# Buttons-Sch-EasyEDA.net
KiCad netlist of a schematic drawn in EasyEDA
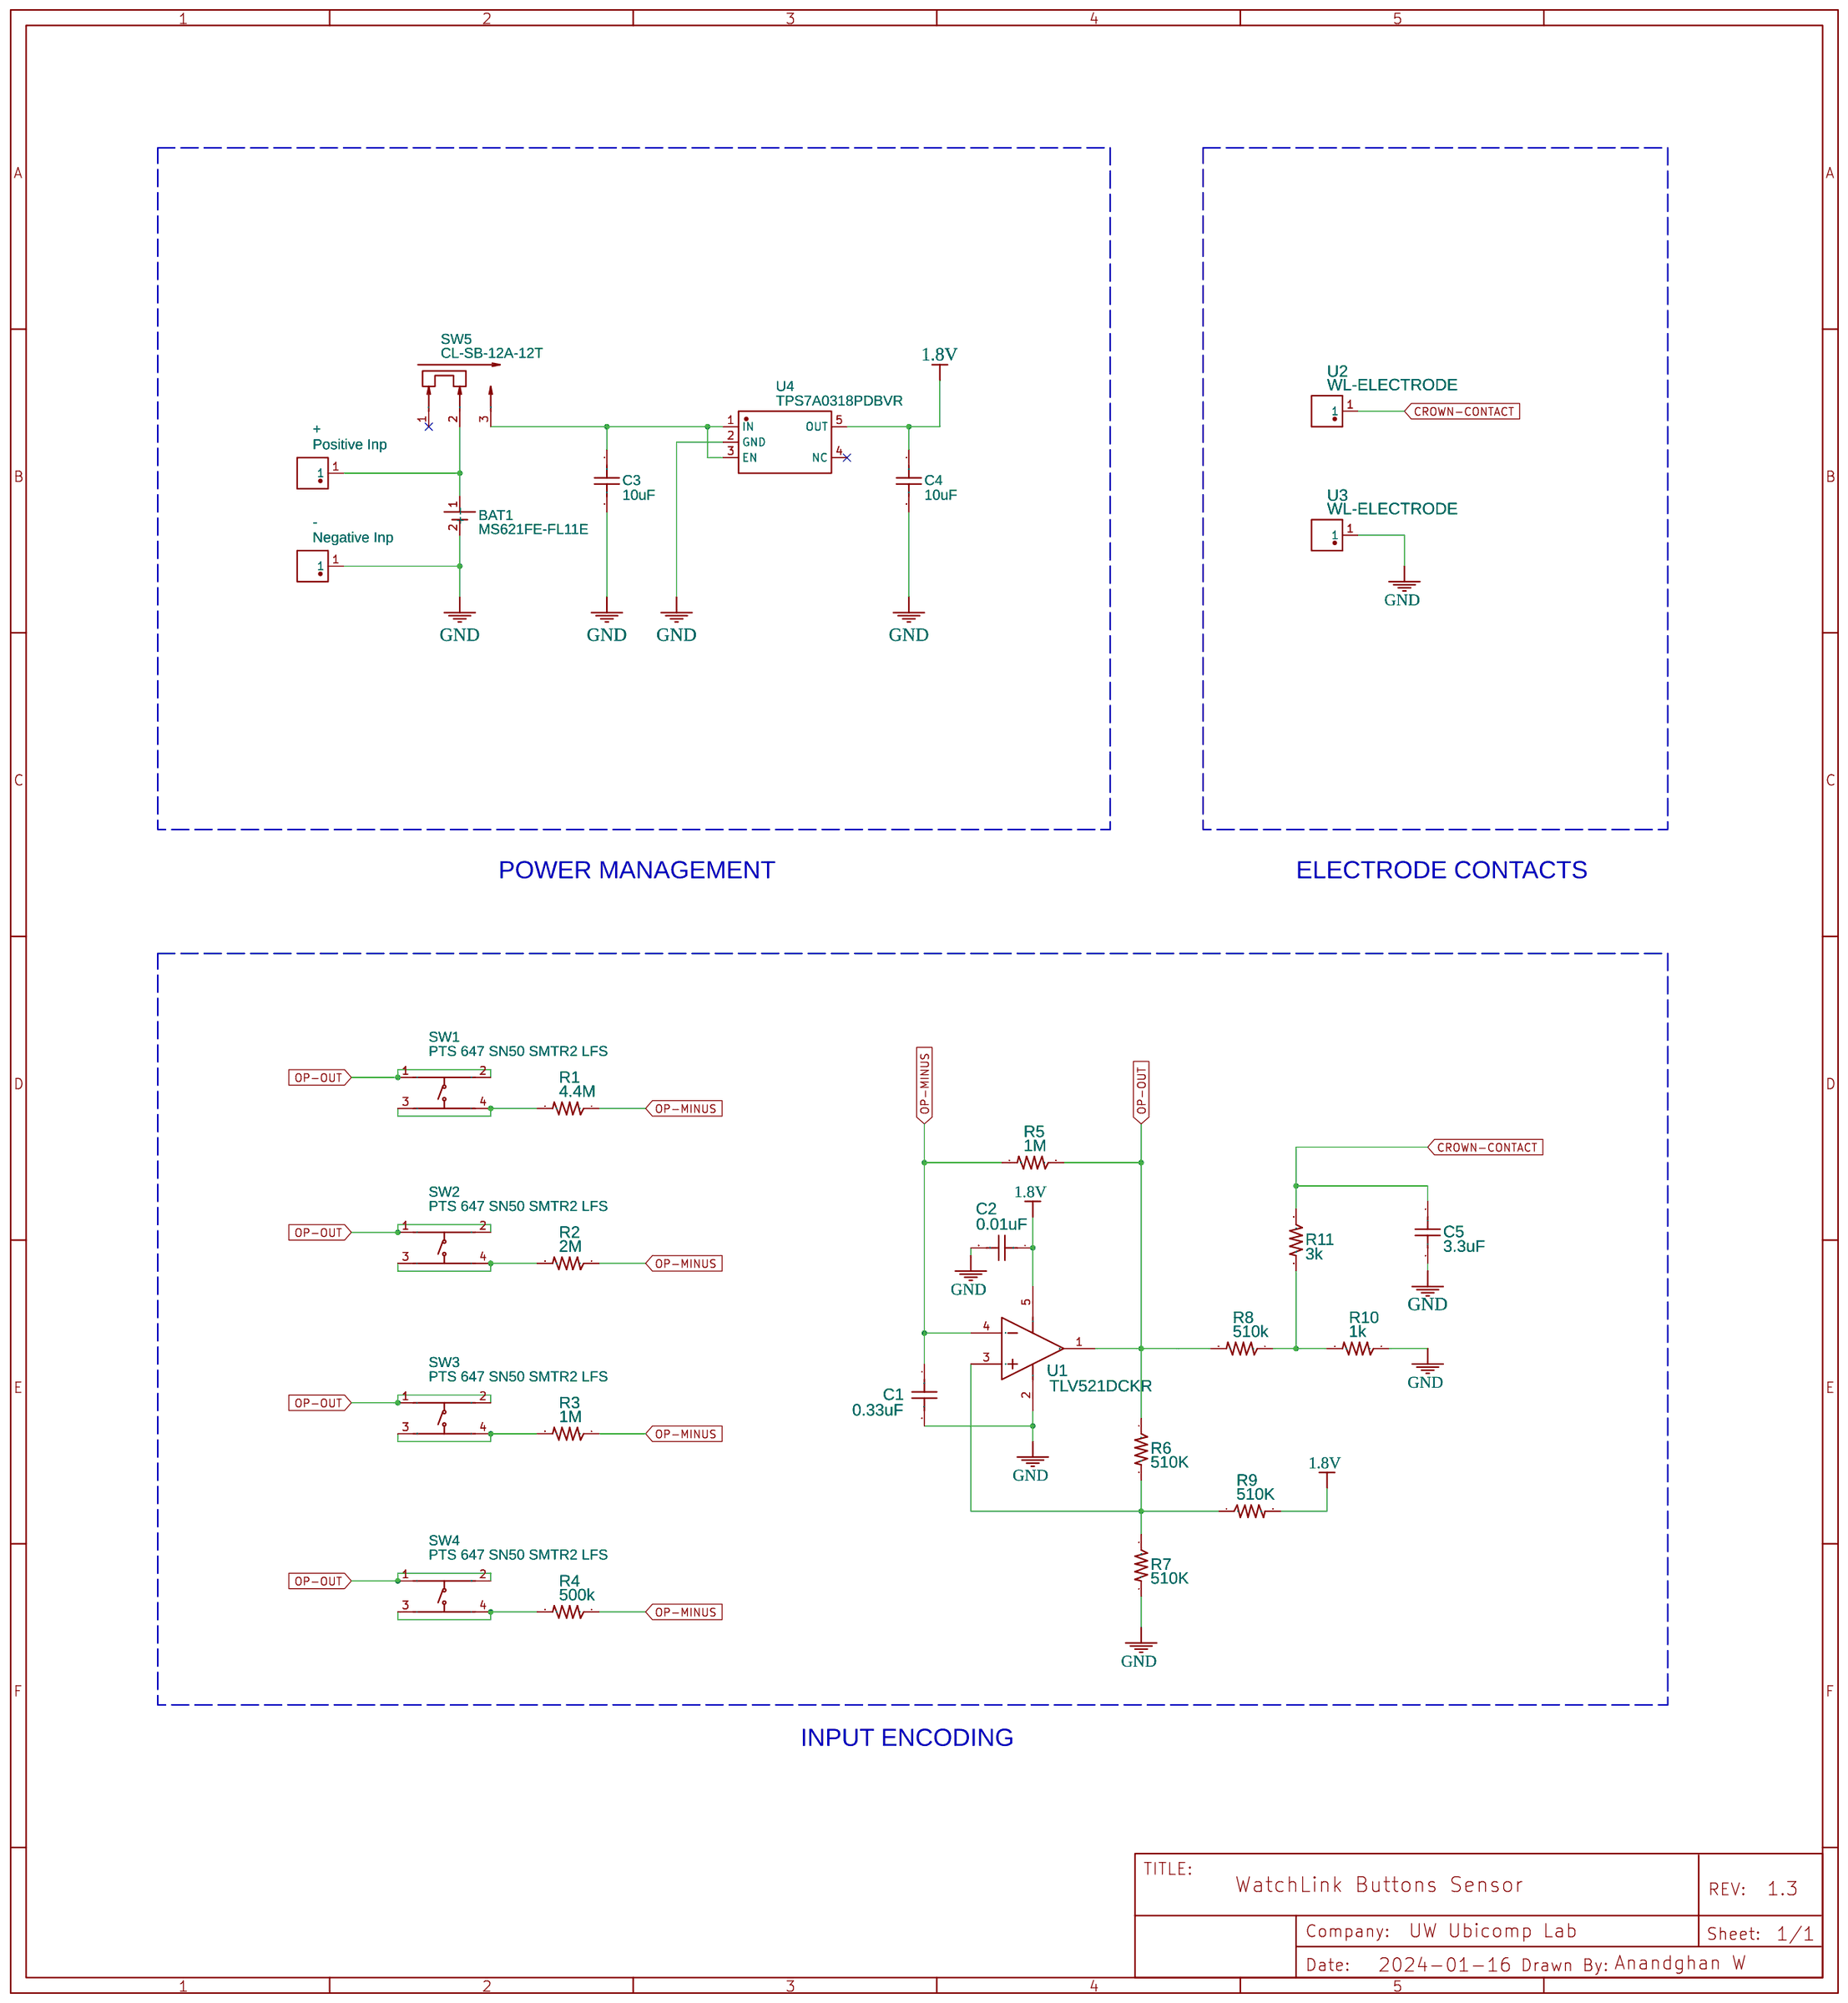
[diagram p0: schematic sheet]

(export (version "E")
  (design (tool "Eeschema 10.0.6"))
  (components
    (comp (ref "+")
      (value "Positive Inp")
      (fields (field (name "Manufacturer Part") "POGO pin探针"))
      (libsource (lib "") (part "WL-ELECTRODE_1"))
    )
    (comp (ref "-")
      (value "Negative Inp")
      (fields (field (name "Manufacturer Part") "POGO pin探针"))
      (libsource (lib "") (part "WL-ELECTRODE_2"))
    )
    (comp (ref "BAT1")
      (value "MS621FE-FL11E")
      (fields (field (name "Manufacturer Part") "ML621 / ML614") (field (name "Manufacturer") "Panasonic"))
      (libsource (lib "") (part "ML614 / ML621 - COIN CELL"))
    )
    (comp (ref "C1")
      (value "0.33uF")
      (fields
        (field (name "Manufacturer Part") "CC0402JRX7R8BB473")
        (field (name "Manufacturer") "YAGEO(国巨)")
      )
      (libsource (lib "") (part "CC0402JRX7R8BB473"))
    )
    (comp (ref "C2")
      (value "0.01uF")
      (fields
        (field (name "Manufacturer Part") "CC0402JRX7R8BB473")
        (field (name "Manufacturer") "YAGEO(国巨)")
      )
      (libsource (lib "") (part "CC0402JRX7R8BB473_1"))
    )
    (comp (ref "C3")
      (value "10uF")
      (fields
        (field (name "Manufacturer Part") "CC0402JRX7R8BB473")
        (field (name "Manufacturer") "YAGEO(国巨)")
      )
      (libsource (lib "") (part "CC0402JRX7R8BB473"))
    )
    (comp (ref "C4")
      (value "10uF")
      (fields
        (field (name "Manufacturer Part") "CC0402JRX7R8BB473")
        (field (name "Manufacturer") "YAGEO(国巨)")
      )
      (libsource (lib "") (part "CC0402JRX7R8BB473"))
    )
    (comp (ref "C5")
      (value "3.3uF")
      (fields
        (field (name "Manufacturer Part") "CC0402JRX7R8BB473")
        (field (name "Manufacturer") "YAGEO(国巨)")
      )
      (libsource (lib "") (part "CC0402JRX7R8BB473"))
    )
    (comp (ref "R1") (value "4.4M") (libsource (lib "") (part "R-US_R0402_2")))
    (comp (ref "R2") (value "2M") (libsource (lib "") (part "R-US_R0402_2")))
    (comp (ref "R3") (value "1M") (libsource (lib "") (part "R-US_R0402_2")))
    (comp (ref "R4") (value "500k") (libsource (lib "") (part "R-US_R0402_2")))
    (comp (ref "R5") (value "1M") (libsource (lib "") (part "R-US_R0402_2")))
    (comp (ref "R6") (value "510K") (libsource (lib "") (part "R-US_R0402")))
    (comp (ref "R7") (value "510K") (libsource (lib "") (part "R-US_R0402")))
    (comp (ref "R8") (value "510k") (libsource (lib "") (part "R-US_R0402_2")))
    (comp (ref "R9") (value "510K") (libsource (lib "") (part "R-US_R0402_1")))
    (comp (ref "R10") (value "1k") (libsource (lib "") (part "R-US_R0402_2")))
    (comp (ref "R11") (value "3k") (libsource (lib "") (part "R-US_R0402")))
    (comp (ref "SW1")
      (value "PTS 647 SN50 SMTR2 LFS")
      (fields (field (name "Manufacturer Part") "PTS647SN50SMTR2LFS") (field (name "Manufacturer") "C&K"))
      (libsource (lib "") (part "PTS 647 SN50 SMTR2 LFS"))
    )
    (comp (ref "SW2")
      (value "PTS 647 SN50 SMTR2 LFS")
      (fields (field (name "Manufacturer Part") "PTS647SN50SMTR2LFS") (field (name "Manufacturer") "C&K"))
      (libsource (lib "") (part "PTS 647 SN50 SMTR2 LFS"))
    )
    (comp (ref "SW3")
      (value "PTS 647 SN50 SMTR2 LFS")
      (fields (field (name "Manufacturer Part") "PTS647SN50SMTR2LFS") (field (name "Manufacturer") "C&K"))
      (libsource (lib "") (part "PTS 647 SN50 SMTR2 LFS"))
    )
    (comp (ref "SW4")
      (value "PTS 647 SN50 SMTR2 LFS")
      (fields (field (name "Manufacturer Part") "PTS647SN50SMTR2LFS") (field (name "Manufacturer") "C&K"))
      (libsource (lib "") (part "PTS 647 SN50 SMTR2 LFS"))
    )
    (comp (ref "SW5")
      (value "CL-SB-12A-12T")
      (fields (field (name "Manufacturer") "NIDEC(尼得科)"))
      (libsource (lib "") (part "CL-SB-12A-12T"))
    )
    (comp (ref "U1")
      (value "TLV521DCKR")
      (fields (field (name "Manufacturer") "TI(德州仪器)"))
      (libsource (lib "") (part "TLV521DCKR"))
    )
    (comp (ref "U2")
      (value "WL-ELECTRODE")
      (fields (field (name "Manufacturer Part") "POGO pin探针"))
      (libsource (lib "") (part "WL-ELECTRODE"))
    )
    (comp (ref "U3")
      (value "WL-ELECTRODE")
      (fields (field (name "Manufacturer Part") "POGO pin探针"))
      (libsource (lib "") (part "WL-ELECTRODE"))
    )
    (comp (ref "U4")
      (value "TPS7A0318PDBVR")
      (fields (field (name "Manufacturer") "TI(德州仪器)"))
      (libsource (lib "") (part "TPS7A0318PDBVR"))
    )
  )
  (nets
    (net (code "1") (name "1.8V") (class "Default")
      (node (ref "C2") (pin "1") (pinfunction "1_1") (pintype "unspecified"))
      (node (ref "C4") (pin "1") (pinfunction "1_1") (pintype "unspecified"))
      (node (ref "R9") (pin "2") (pinfunction "2_2") (pintype "unspecified"))
      (node (ref "U1") (pin "5") (pinfunction "V+_5") (pintype "passive"))
      (node (ref "U4") (pin "5") (pinfunction "OUT_5") (pintype "unspecified"))
    )
    (net (code "2") (name "CROWN-CONTACT") (class "Default")
      (node (ref "C5") (pin "1") (pinfunction "1_1") (pintype "unspecified"))
      (node (ref "R11") (pin "1") (pinfunction "1_1") (pintype "unspecified"))
      (node (ref "U2") (pin "1") (pinfunction "1_1") (pintype "unspecified"))
    )
    (net (code "3") (name "GND") (class "Default")
      (node (ref "-") (pin "1") (pinfunction "1_1") (pintype "unspecified"))
      (node (ref "BAT1") (pin "2") (pinfunction "-_2") (pintype "unspecified"))
      (node (ref "C1") (pin "2") (pinfunction "2_2") (pintype "unspecified"))
      (node (ref "C2") (pin "2") (pinfunction "2_2") (pintype "unspecified"))
      (node (ref "C3") (pin "2") (pinfunction "2_2") (pintype "unspecified"))
      (node (ref "C4") (pin "2") (pinfunction "2_2") (pintype "unspecified"))
      (node (ref "C5") (pin "2") (pinfunction "2_2") (pintype "unspecified"))
      (node (ref "R10") (pin "1") (pinfunction "1_1") (pintype "unspecified"))
      (node (ref "R7") (pin "2") (pinfunction "2_2") (pintype "unspecified"))
      (node (ref "U1") (pin "2") (pinfunction "V-_2") (pintype "passive"))
      (node (ref "U3") (pin "1") (pinfunction "1_1") (pintype "unspecified"))
      (node (ref "U4") (pin "2") (pinfunction "GND_2") (pintype "unspecified"))
    )
    (net (code "4") (name "Net-(BAT1-+)") (class "Default")
      (node (ref "+") (pin "1") (pinfunction "1_1") (pintype "unspecified"))
      (node (ref "BAT1") (pin "1") (pinfunction "+_1") (pintype "unspecified"))
      (node (ref "SW5") (pin "2") (pinfunction "2_2") (pintype "unspecified"))
    )
    (net (code "5") (name "Net-(R1-Pad2)") (class "Default")
      (node (ref "R1") (pin "2") (pinfunction "2_2") (pintype "unspecified"))
      (node (ref "SW1") (pin "3") (pinfunction "3_3") (pintype "unspecified"))
      (node (ref "SW1") (pin "4") (pinfunction "4_4") (pintype "unspecified"))
    )
    (net (code "6") (name "Net-(R2-Pad2)") (class "Default")
      (node (ref "R2") (pin "2") (pinfunction "2_2") (pintype "unspecified"))
      (node (ref "SW2") (pin "3") (pinfunction "3_3") (pintype "unspecified"))
      (node (ref "SW2") (pin "4") (pinfunction "4_4") (pintype "unspecified"))
    )
    (net (code "7") (name "Net-(R3-Pad2)") (class "Default")
      (node (ref "R3") (pin "2") (pinfunction "2_2") (pintype "unspecified"))
      (node (ref "SW3") (pin "3") (pinfunction "3_3") (pintype "unspecified"))
      (node (ref "SW3") (pin "4") (pinfunction "4_4") (pintype "unspecified"))
    )
    (net (code "8") (name "Net-(R4-Pad2)") (class "Default")
      (node (ref "R4") (pin "2") (pinfunction "2_2") (pintype "unspecified"))
      (node (ref "SW4") (pin "3") (pinfunction "3_3") (pintype "unspecified"))
      (node (ref "SW4") (pin "4") (pinfunction "4_4") (pintype "unspecified"))
    )
    (net (code "9") (name "Net-(R10-Pad2)") (class "Default")
      (node (ref "R10") (pin "2") (pinfunction "2_2") (pintype "unspecified"))
      (node (ref "R11") (pin "2") (pinfunction "2_2") (pintype "unspecified"))
      (node (ref "R8") (pin "1") (pinfunction "1_1") (pintype "unspecified"))
    )
    (net (code "10") (name "Net-(U1-IN+)") (class "Default")
      (node (ref "R6") (pin "2") (pinfunction "2_2") (pintype "unspecified"))
      (node (ref "R7") (pin "1") (pinfunction "1_1") (pintype "unspecified"))
      (node (ref "R9") (pin "1") (pinfunction "1_1") (pintype "unspecified"))
      (node (ref "U1") (pin "3") (pinfunction "IN+_3") (pintype "unspecified"))
    )
    (net (code "11") (name "Net-(U4-EN)") (class "Default")
      (node (ref "C3") (pin "1") (pinfunction "1_1") (pintype "unspecified"))
      (node (ref "SW5") (pin "3") (pinfunction "3_3") (pintype "unspecified"))
      (node (ref "U4") (pin "1") (pinfunction "IN_1") (pintype "unspecified"))
      (node (ref "U4") (pin "3") (pinfunction "EN_3") (pintype "unspecified"))
    )
    (net (code "12") (name "OP-MINUS") (class "Default")
      (node (ref "C1") (pin "1") (pinfunction "1_1") (pintype "unspecified"))
      (node (ref "R1") (pin "1") (pinfunction "1_1") (pintype "unspecified"))
      (node (ref "R2") (pin "1") (pinfunction "1_1") (pintype "unspecified"))
      (node (ref "R3") (pin "1") (pinfunction "1_1") (pintype "unspecified"))
      (node (ref "R4") (pin "1") (pinfunction "1_1") (pintype "unspecified"))
      (node (ref "R5") (pin "2") (pinfunction "2_2") (pintype "unspecified"))
      (node (ref "U1") (pin "4") (pinfunction "IN-_4") (pintype "unspecified"))
    )
    (net (code "13") (name "OP-OUT") (class "Default")
      (node (ref "R5") (pin "1") (pinfunction "1_1") (pintype "unspecified"))
      (node (ref "R6") (pin "1") (pinfunction "1_1") (pintype "unspecified"))
      (node (ref "R8") (pin "2") (pinfunction "2_2") (pintype "unspecified"))
      (node (ref "SW1") (pin "1") (pinfunction "1_1") (pintype "unspecified"))
      (node (ref "SW1") (pin "2") (pinfunction "2_2") (pintype "unspecified"))
      (node (ref "SW2") (pin "1") (pinfunction "1_1") (pintype "unspecified"))
      (node (ref "SW2") (pin "2") (pinfunction "2_2") (pintype "unspecified"))
      (node (ref "SW3") (pin "1") (pinfunction "1_1") (pintype "unspecified"))
      (node (ref "SW3") (pin "2") (pinfunction "2_2") (pintype "unspecified"))
      (node (ref "SW4") (pin "1") (pinfunction "1_1") (pintype "unspecified"))
      (node (ref "SW4") (pin "2") (pinfunction "2_2") (pintype "unspecified"))
      (node (ref "U1") (pin "1") (pinfunction "OUT_1") (pintype "output"))
    )
    (net (code "14") (name "unconnected-(SW5-Pad1)") (class "Default")
      (node (ref "SW5") (pin "1") (pinfunction "1_1") (pintype "unspecified+no_connect"))
    )
    (net (code "15") (name "unconnected-(U4-NC-Pad4)") (class "Default")
      (node (ref "U4") (pin "4") (pinfunction "NC_4") (pintype "unspecified+no_connect"))
    )
  )
)
